# SCHcadcamcuoiki.net
KiCad netlist of a schematic drawn in Altium Designer
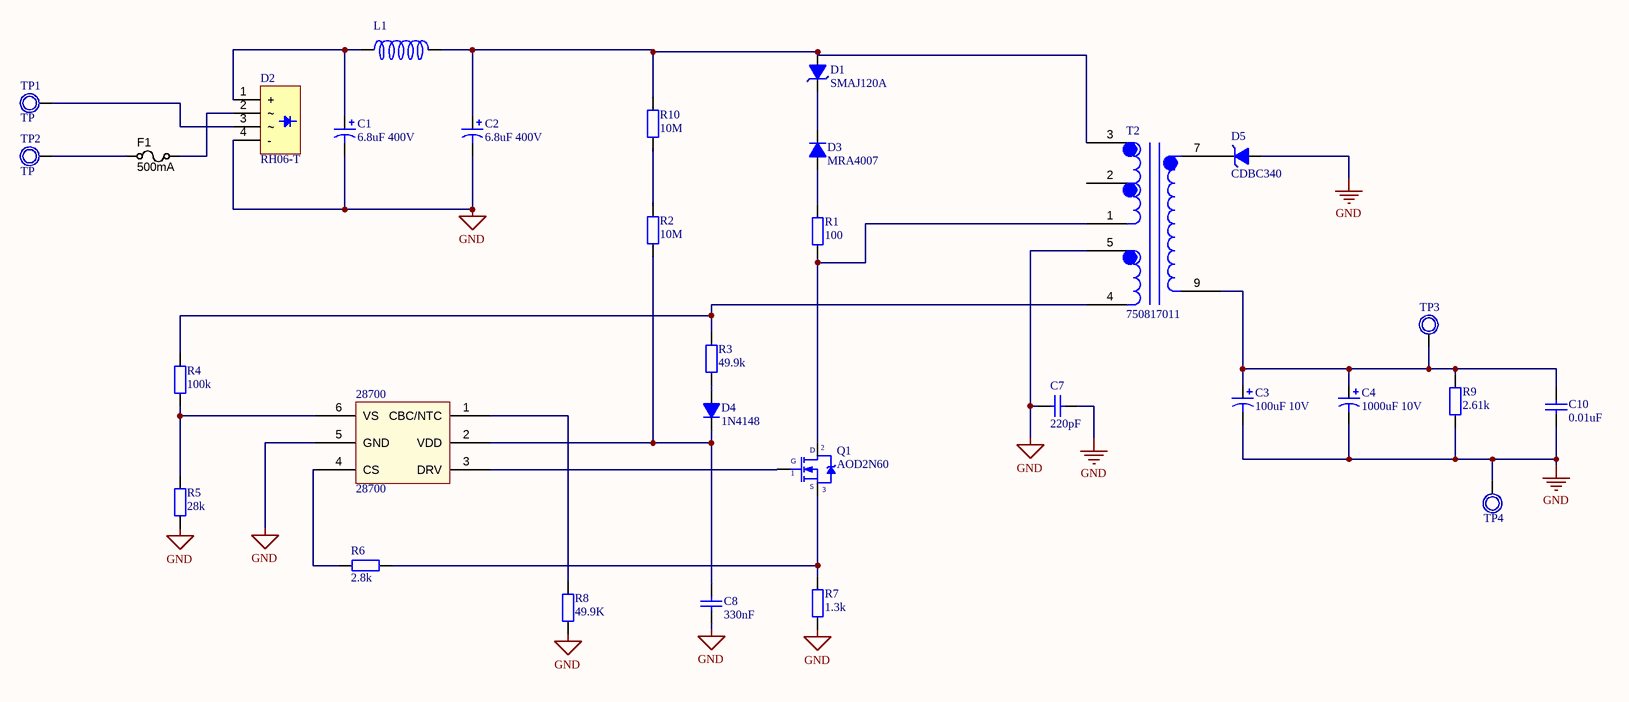
[diagram p0: SCHcadcamcuoiki.SchDoc]

(export (version "E")
  (design (tool "Eeschema 10.0.6"))
  (components
    (comp (ref "28700") (value "28700") (footprint "SOT23(1)") (libsource (lib "Schlib2") (part "28700")))
    (comp (ref "C1")
      (value "6.8uF 400V")
      (footprint "C3MM")
      (description "Polarized Capacitor (Axial)")
      (fields (field (name "PUBLISHER") "Altium Limited"))
      (libsource (lib "Devzone_SCHLib") (part "Cap Pol 3mm"))
    )
    (comp (ref "C2")
      (value "6.8uF 400V")
      (footprint "C3MM")
      (description "Polarized Capacitor (Axial)")
      (fields (field (name "PUBLISHER") "Altium Limited"))
      (libsource (lib "Devzone_SCHLib") (part "Cap Pol 3mm"))
    )
    (comp (ref "C3")
      (value "100uF 10V")
      (footprint "C5mm")
      (description "Polarized Capacitor (Axial)")
      (fields (field (name "PUBLISHER") "Altium Limited"))
      (libsource (lib "Devzone_SCHLib") (part "Cap Pol 5mm"))
    )
    (comp (ref "C4")
      (value "1000uF 10V")
      (footprint "C5mm")
      (description "Polarized Capacitor (Axial)")
      (fields (field (name "PUBLISHER") "Altium Limited"))
      (libsource (lib "Devzone_SCHLib") (part "Cap Pol 5mm"))
    )
    (comp (ref "C7")
      (value "220pF")
      (footprint "tu tantalum dip5.08")
      (description "Cắm")
      (libsource (lib "Altium_Lib_by_KhueNguyenCreator") (part "Tu tantalum 220pF 50V 5% DIP5.08"))
    )
    (comp (ref "C8")
      (value "330nF")
      (footprint "Tu tantalum dip5.08")
      (description "Cắm")
      (libsource (lib "Altium_Lib_by_KhueNguyenCreator") (part "Tu tantalum 330nF 50V 20% DIP5.08"))
    )
    (comp (ref "C10")
      (value "0.01uF")
      (footprint "tu gom")
      (description "Cắm")
      (libsource (lib "Altium_Lib_by_KhueNguyenCreator") (part "Tu gom 100 50V"))
    )
    (comp (ref "D1")
      (value "SMAJ120A")
      (footprint "DIODE ZENNER SMD SOD80")
      (description "Cắm")
      (libsource (lib "Altium_Lib_by_KhueNguyenCreator") (part "Diode Zener 24V"))
    )
    (comp (ref "D2")
      (value "RH06-T")
      (footprint "DIODE CAU 10A CAM")
      (description "Cắm")
      (libsource (lib "Altium_Lib_by_KhueNguyenCreator") (part "Diode CAU 10A"))
    )
    (comp (ref "D3")
      (value "MRA4007")
      (footprint "DIODE 7A")
      (description "Cắm")
      (libsource (lib "Altium_Lib_by_KhueNguyenCreator") (part "Diode 6A 1000V"))
    )
    (comp (ref "D4")
      (value "1N4148")
      (footprint "DIODE 0.5A")
      (description "Cắm")
      (libsource (lib "Altium_Lib_by_KhueNguyenCreator") (part "Diode 1N4148"))
    )
    (comp (ref "D5")
      (value "CDBC340")
      (footprint "DIODE ZENNER SMD SOD80")
      (description "Cắm")
      (libsource (lib "Altium_Lib_by_KhueNguyenCreator") (part "Diode Zener 24V"))
    )
    (comp (ref "F1")
      (value "500mA")
      (footprint "RESC1608X55N")
      (description "Fuse 500mA 32VDC 0603 SMD")
      (fields (field (name "Comment") "Fast Acting"))
      (libsource (lib "my Library") (part "FUSE_FAST_500mA_0603"))
    )
    (comp (ref "L1")
      (value "~")
      (footprint "CUON CAM 200mil")
      (libsource (lib "my Library") (part "Conductor"))
    )
    (comp (ref "Q1")
      (value "AOD2N60")
      (footprint "QTO-220")
      (description "MOSFET N - CHANNEL 500V - 0.75 - 8A - TO-220")
      (libsource (lib "Devzone_SCHLib") (part "IRF840"))
    )
    (comp (ref "R1")
      (value "100")
      (footprint "tro vach 1/4w")
      (description "Cắm")
      (libsource (lib "Altium_Lib_by_KhueNguyenCreator") (part "Tro Vach 1/4W 5% 100k"))
    )
    (comp (ref "R2")
      (value "10M")
      (footprint "tro vach 1/4w")
      (description "Cắm")
      (libsource (lib "Dien Tro") (part "Tro Vach 1/4W 5% 10M"))
    )
    (comp (ref "R3")
      (value "49.9k")
      (footprint "tro vach 1/4w")
      (description "Cắm")
      (libsource (lib "Altium_Lib_by_KhueNguyenCreator") (part "Tro Vach 1/4W 5% 51k"))
    )
    (comp (ref "R4")
      (value "100k")
      (footprint "tro vach 1/4w")
      (description "Cắm")
      (libsource (lib "Altium_Lib_by_KhueNguyenCreator") (part "Tro Vach 1/4W 5% 100k"))
    )
    (comp (ref "R5")
      (value "28k")
      (footprint "tro vach 1/4w")
      (description "Cắm")
      (libsource (lib "Altium_Lib_by_KhueNguyenCreator") (part "Tro Vach 1/4W 5% 30k"))
    )
    (comp (ref "R6")
      (value "2.8k")
      (footprint "tro vach 1/4w")
      (description "Cắm")
      (libsource (lib "Altium_Lib_by_KhueNguyenCreator") (part "Tro Vach 1/4W 1% 3k"))
    )
    (comp (ref "R7")
      (value "1.3k")
      (footprint "tro vach 1/4w")
      (description "Cắm")
      (libsource (lib "Altium_Lib_by_KhueNguyenCreator") (part "Tro Vach 1/4W 5% 1.5k"))
    )
    (comp (ref "R8")
      (value "49.9K")
      (footprint "tro vach 1/4w")
      (description "Cắm")
      (libsource (lib "Altium_Lib_by_KhueNguyenCreator") (part "Tro Vach 1/4W 5% 51k"))
    )
    (comp (ref "R9")
      (value "2.61k")
      (footprint "tro vach 1/4w")
      (description "Cắm")
      (libsource (lib "Altium_Lib_by_KhueNguyenCreator") (part "Tro Vach 1/4W 5% 2.7k"))
    )
    (comp (ref "R10")
      (value "10M")
      (footprint "tro vach 1/4w")
      (description "Cắm")
      (libsource (lib "Dien Tro") (part "Tro Vach 1/4W 5% 10M"))
    )
    (comp (ref "T2")
      (value "750817011")
      (footprint "750817011")
      (libsource (lib "bien_ap") (part "750817011"))
    )
    (comp (ref "TP1")
      (value "TP")
      (footprint "TP1")
      (description "Test Point")
      (libsource (lib "") (part "TP1_1"))
    )
    (comp (ref "TP2")
      (value "TP")
      (footprint "TP1")
      (description "Test Point")
      (libsource (lib "") (part "TP1_1"))
    )
    (comp (ref "TP3")
      (value "~")
      (footprint "TP1")
      (description "Test Point")
      (libsource (lib "SCH_Lib_Devzone") (part "TP1"))
    )
    (comp (ref "TP4")
      (value "~")
      (footprint "TP1")
      (description "Test Point")
      (libsource (lib "") (part "TP1_2"))
    )
  )
  (nets
    (net (code "1") (name "GND") (class "Default")
      (node (ref "28700") (pin "5") (pinfunction "GND_5") (pintype "passive"))
      (node (ref "C1") (pin "2") (pinfunction "2_2") (pintype "passive"))
      (node (ref "C10") (pin "2") (pinfunction "2_2") (pintype "passive"))
      (node (ref "C2") (pin "2") (pinfunction "2_2") (pintype "passive"))
      (node (ref "C3") (pin "2") (pinfunction "2_2") (pintype "passive"))
      (node (ref "C4") (pin "2") (pinfunction "2_2") (pintype "passive"))
      (node (ref "C7") (pin "1") (pinfunction "1_1") (pintype "passive"))
      (node (ref "C7") (pin "2") (pinfunction "2_2") (pintype "passive"))
      (node (ref "C8") (pin "2") (pinfunction "2_2") (pintype "passive"))
      (node (ref "D2") (pin "4") (pinfunction "-_4") (pintype "passive"))
      (node (ref "D5") (pin "1") (pinfunction "A_1") (pintype "passive"))
      (node (ref "R5") (pin "1") (pinfunction "1_1") (pintype "passive"))
      (node (ref "R7") (pin "1") (pinfunction "1_1") (pintype "passive"))
      (node (ref "R8") (pin "1") (pinfunction "1_1") (pintype "passive"))
      (node (ref "R9") (pin "1") (pinfunction "1_1") (pintype "passive"))
      (node (ref "T2") (pin "5") (pinfunction "5_5") (pintype "passive"))
      (node (ref "TP4") (pin "1") (pinfunction "1_1") (pintype "passive"))
    )
    (net (code "2") (name "Net-(28700-CBC{slash}NTC)") (class "Default")
      (node (ref "28700") (pin "1") (pinfunction "CBC/NTC_1") (pintype "passive"))
      (node (ref "R8") (pin "2") (pinfunction "2_2") (pintype "passive"))
    )
    (net (code "3") (name "Net-(28700-CS)") (class "Default")
      (node (ref "28700") (pin "4") (pinfunction "CS_4") (pintype "passive"))
      (node (ref "R6") (pin "1") (pinfunction "1_1") (pintype "passive"))
    )
    (net (code "4") (name "Net-(28700-DRV)") (class "Default")
      (node (ref "28700") (pin "3") (pinfunction "DRV_3") (pintype "passive"))
      (node (ref "Q1") (pin "1") (pinfunction "G_1") (pintype "passive"))
    )
    (net (code "5") (name "Net-(28700-VDD)") (class "Default")
      (node (ref "28700") (pin "2") (pinfunction "VDD_2") (pintype "passive"))
      (node (ref "C8") (pin "1") (pinfunction "1_1") (pintype "passive"))
      (node (ref "D4") (pin "2") (pinfunction "K_2") (pintype "passive"))
      (node (ref "R2") (pin "1") (pinfunction "1_1") (pintype "passive"))
    )
    (net (code "6") (name "Net-(28700-VS)") (class "Default")
      (node (ref "28700") (pin "6") (pinfunction "VS_6") (pintype "passive"))
      (node (ref "R4") (pin "1") (pinfunction "1_1") (pintype "passive"))
      (node (ref "R5") (pin "2") (pinfunction "2_2") (pintype "passive"))
    )
    (net (code "7") (name "Net-(C10-Pad1)") (class "Default")
      (node (ref "C10") (pin "1") (pinfunction "1_1") (pintype "passive"))
      (node (ref "C3") (pin "1") (pinfunction "1_1") (pintype "passive"))
      (node (ref "C4") (pin "1") (pinfunction "1_1") (pintype "passive"))
      (node (ref "R9") (pin "2") (pinfunction "2_2") (pintype "passive"))
      (node (ref "T2") (pin "9") (pinfunction "9_9") (pintype "passive"))
      (node (ref "TP3") (pin "1") (pinfunction "1_1") (pintype "passive"))
    )
    (net (code "8") (name "Net-(D1-A)") (class "Default")
      (node (ref "C2") (pin "1") (pinfunction "1_1") (pintype "passive"))
      (node (ref "D1") (pin "1") (pinfunction "A_1") (pintype "passive"))
      (node (ref "L1") (pin "2") (pinfunction "2_2") (pintype "passive"))
      (node (ref "R10") (pin "2") (pinfunction "2_2") (pintype "passive"))
      (node (ref "T2") (pin "3") (pinfunction "3_3") (pintype "passive"))
    )
    (net (code "9") (name "Net-(D1-K)") (class "Default")
      (node (ref "D1") (pin "2") (pinfunction "K_2") (pintype "passive"))
      (node (ref "D3") (pin "2") (pinfunction "K_2") (pintype "passive"))
    )
    (net (code "10") (name "Net-(D2-+)") (class "Default")
      (node (ref "C1") (pin "1") (pinfunction "1_1") (pintype "passive"))
      (node (ref "D2") (pin "1") (pinfunction "+_1") (pintype "passive"))
      (node (ref "L1") (pin "1") (pinfunction "1_1") (pintype "passive"))
    )
    (net (code "11") (name "Net-(D2-~-Pad2)") (class "Default")
      (node (ref "D2") (pin "2") (pinfunction "~_2") (pintype "passive"))
      (node (ref "F1") (pin "2") (pinfunction "2_2") (pintype "passive"))
    )
    (net (code "12") (name "Net-(D2-~-Pad3)") (class "Default")
      (node (ref "D2") (pin "3") (pinfunction "~_3") (pintype "passive"))
      (node (ref "TP1") (pin "1") (pinfunction "1_1") (pintype "passive"))
    )
    (net (code "13") (name "Net-(D3-A)") (class "Default")
      (node (ref "D3") (pin "1") (pinfunction "A_1") (pintype "passive"))
      (node (ref "R1") (pin "2") (pinfunction "2_2") (pintype "passive"))
    )
    (net (code "14") (name "Net-(D4-A)") (class "Default")
      (node (ref "D4") (pin "1") (pinfunction "A_1") (pintype "passive"))
      (node (ref "R3") (pin "1") (pinfunction "1_1") (pintype "passive"))
    )
    (net (code "15") (name "Net-(D5-K)") (class "Default")
      (node (ref "D5") (pin "2") (pinfunction "K_2") (pintype "passive"))
      (node (ref "T2") (pin "7") (pinfunction "7_7") (pintype "passive"))
    )
    (net (code "16") (name "Net-(F1-Pad1)") (class "Default")
      (node (ref "F1") (pin "1") (pinfunction "1_1") (pintype "passive"))
      (node (ref "TP2") (pin "1") (pinfunction "1_1") (pintype "passive"))
    )
    (net (code "17") (name "Net-(Q1-D)") (class "Default")
      (node (ref "Q1") (pin "2") (pinfunction "D_2") (pintype "passive"))
      (node (ref "R1") (pin "1") (pinfunction "1_1") (pintype "passive"))
      (node (ref "T2") (pin "1") (pinfunction "1_1") (pintype "passive"))
    )
    (net (code "18") (name "Net-(Q1-S)") (class "Default")
      (node (ref "Q1") (pin "3") (pinfunction "S_3") (pintype "passive"))
      (node (ref "R6") (pin "2") (pinfunction "2_2") (pintype "passive"))
      (node (ref "R7") (pin "2") (pinfunction "2_2") (pintype "passive"))
    )
    (net (code "19") (name "Net-(R3-Pad2)") (class "Default")
      (node (ref "R3") (pin "2") (pinfunction "2_2") (pintype "passive"))
      (node (ref "R4") (pin "2") (pinfunction "2_2") (pintype "passive"))
      (node (ref "T2") (pin "4") (pinfunction "4_4") (pintype "passive"))
    )
    (net (code "20") (name "Net-(R10-Pad1)") (class "Default")
      (node (ref "R10") (pin "1") (pinfunction "1_1") (pintype "passive"))
      (node (ref "R2") (pin "2") (pinfunction "2_2") (pintype "passive"))
    )
    (net (code "21") (name "unconnected-(T2-Pad2)") (class "Default")
      (node (ref "T2") (pin "2") (pinfunction "2_2") (pintype "passive"))
    )
  )
)
